# PDU_Meanwell_LRS.net
KiCad netlist of a schematic drawn in EAGLE
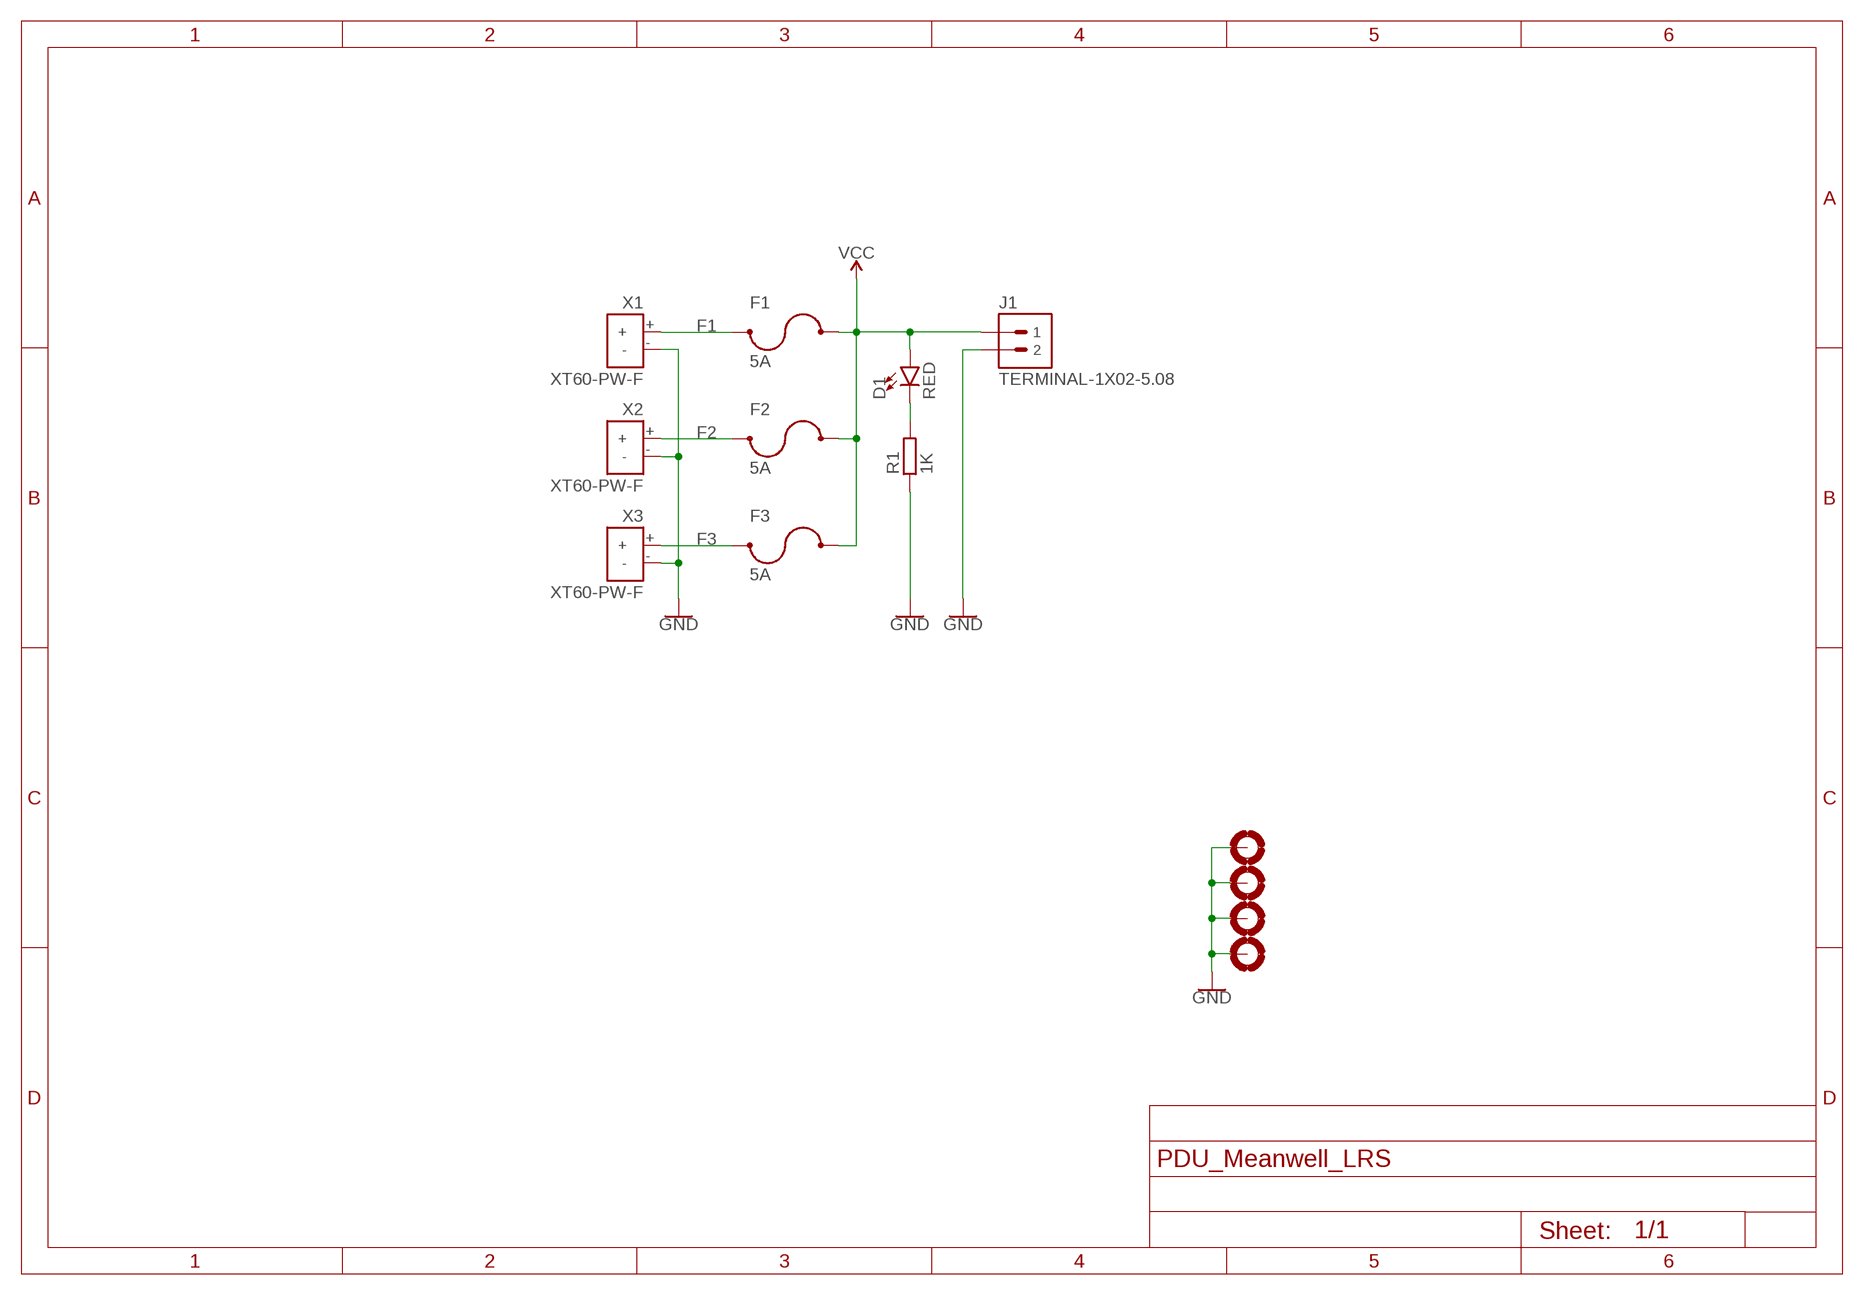
[diagram p0: schematic, sheet 1]

(export (version "E")
  (design (tool "Eeschema 10.0.6"))
  (components
    (comp (ref "D1")
      (value "RED")
      (footprint "eagle-import:LED5MM")
      (libsource (lib "eagle-import") (part "LED5MM"))
    )
    (comp (ref "F1")
      (value "5A")
      (footprint "eagle-import:CAR-FUSE-MEDIUM")
      (libsource (lib "eagle-import") (part "FUSE-HOLDERCAR-MEDIUM"))
    )
    (comp (ref "F2")
      (value "5A")
      (footprint "eagle-import:CAR-FUSE-MEDIUM")
      (libsource (lib "eagle-import") (part "FUSE-HOLDERCAR-MEDIUM"))
    )
    (comp (ref "F3")
      (value "5A")
      (footprint "eagle-import:CAR-FUSE-MEDIUM")
      (libsource (lib "eagle-import") (part "FUSE-HOLDERCAR-MEDIUM"))
    )
    (comp (ref "H1")
      (value "MOUNTHOLE-PAD3.2")
      (footprint "eagle-import:3.2-PAD")
      (libsource (lib "eagle-import") (part "MOUNTHOLE-PAD3.2"))
    )
    (comp (ref "H2")
      (value "MOUNTHOLE-PAD3.2")
      (footprint "eagle-import:3.2-PAD")
      (libsource (lib "eagle-import") (part "MOUNTHOLE-PAD3.2"))
    )
    (comp (ref "H3")
      (value "MOUNTHOLE-PAD3.2")
      (footprint "eagle-import:3.2-PAD")
      (libsource (lib "eagle-import") (part "MOUNTHOLE-PAD3.2"))
    )
    (comp (ref "H4")
      (value "MOUNTHOLE-PAD3.2")
      (footprint "eagle-import:3.2-PAD")
      (libsource (lib "eagle-import") (part "MOUNTHOLE-PAD3.2"))
    )
    (comp (ref "J1")
      (value "TERMINAL-1X02-5.08")
      (footprint "eagle-import:TERMINAL-5.08-2P")
      (libsource (lib "eagle-import") (part "TERMINAL-1X02-5.08"))
    )
    (comp (ref "R1")
      (value "1K")
      (footprint "eagle-import:R0603")
      (libsource (lib "eagle-import") (part "RESISTOR0603"))
    )
    (comp (ref "X1")
      (value "XT60-PW-F")
      (footprint "eagle-import:XT60-PW-F")
      (libsource (lib "eagle-import") (part "XT60-PW-F"))
    )
    (comp (ref "X2")
      (value "XT60-PW-F")
      (footprint "eagle-import:XT60-PW-F")
      (libsource (lib "eagle-import") (part "XT60-PW-F"))
    )
    (comp (ref "X3")
      (value "XT60-PW-F")
      (footprint "eagle-import:XT60-PW-F")
      (libsource (lib "eagle-import") (part "XT60-PW-F"))
    )
  )
  (nets
    (net (code "1") (name "/F1") (class "Default")
      (node (ref "F1") (pin "1@1") (pinfunction "1_1@1") (pintype "bidirectional"))
      (node (ref "F1") (pin "1@2") (pinfunction "1_1@2") (pintype "bidirectional"))
      (node (ref "X1") (pin "+") (pinfunction "+_+") (pintype "power_in"))
    )
    (net (code "2") (name "/F2") (class "Default")
      (node (ref "F2") (pin "1@1") (pinfunction "1_1@1") (pintype "bidirectional"))
      (node (ref "F2") (pin "1@2") (pinfunction "1_1@2") (pintype "bidirectional"))
      (node (ref "X2") (pin "+") (pinfunction "+_+") (pintype "power_in"))
    )
    (net (code "3") (name "/F3") (class "Default")
      (node (ref "F3") (pin "1@1") (pinfunction "1_1@1") (pintype "bidirectional"))
      (node (ref "F3") (pin "1@2") (pinfunction "1_1@2") (pintype "bidirectional"))
      (node (ref "X3") (pin "+") (pinfunction "+_+") (pintype "power_in"))
    )
    (net (code "4") (name "GND") (class "Default")
      (node (ref "H1") (pin "B3,2") (pinfunction "MOUNT_B3,2") (pintype "passive"))
      (node (ref "H2") (pin "B3,2") (pinfunction "MOUNT_B3,2") (pintype "passive"))
      (node (ref "H3") (pin "B3,2") (pinfunction "MOUNT_B3,2") (pintype "passive"))
      (node (ref "H4") (pin "B3,2") (pinfunction "MOUNT_B3,2") (pintype "passive"))
      (node (ref "J1") (pin "P$2") (pinfunction "2_P$2") (pintype "passive"))
      (node (ref "R1") (pin "1") (pinfunction "1_1") (pintype "passive"))
      (node (ref "X1") (pin "-") (pinfunction "-_-") (pintype "power_in"))
      (node (ref "X2") (pin "-") (pinfunction "-_-") (pintype "power_in"))
      (node (ref "X3") (pin "-") (pinfunction "-_-") (pintype "power_in"))
    )
    (net (code "5") (name "Net-(D1-C)") (class "Default")
      (node (ref "D1") (pin "K") (pinfunction "C_K") (pintype "passive"))
      (node (ref "R1") (pin "2") (pinfunction "2_2") (pintype "passive"))
    )
    (net (code "6") (name "VCC") (class "Default")
      (node (ref "D1") (pin "A") (pinfunction "A_A") (pintype "passive"))
      (node (ref "F1") (pin "2@3") (pinfunction "2_2@3") (pintype "bidirectional"))
      (node (ref "F1") (pin "2@4") (pinfunction "2_2@4") (pintype "bidirectional"))
      (node (ref "F2") (pin "2@3") (pinfunction "2_2@3") (pintype "bidirectional"))
      (node (ref "F2") (pin "2@4") (pinfunction "2_2@4") (pintype "bidirectional"))
      (node (ref "F3") (pin "2@3") (pinfunction "2_2@3") (pintype "bidirectional"))
      (node (ref "F3") (pin "2@4") (pinfunction "2_2@4") (pintype "bidirectional"))
      (node (ref "J1") (pin "P$1") (pinfunction "1_P$1") (pintype "passive"))
    )
  )
)
